# SMeter_RevB.net
KiCad netlist of a schematic drawn in EAGLE
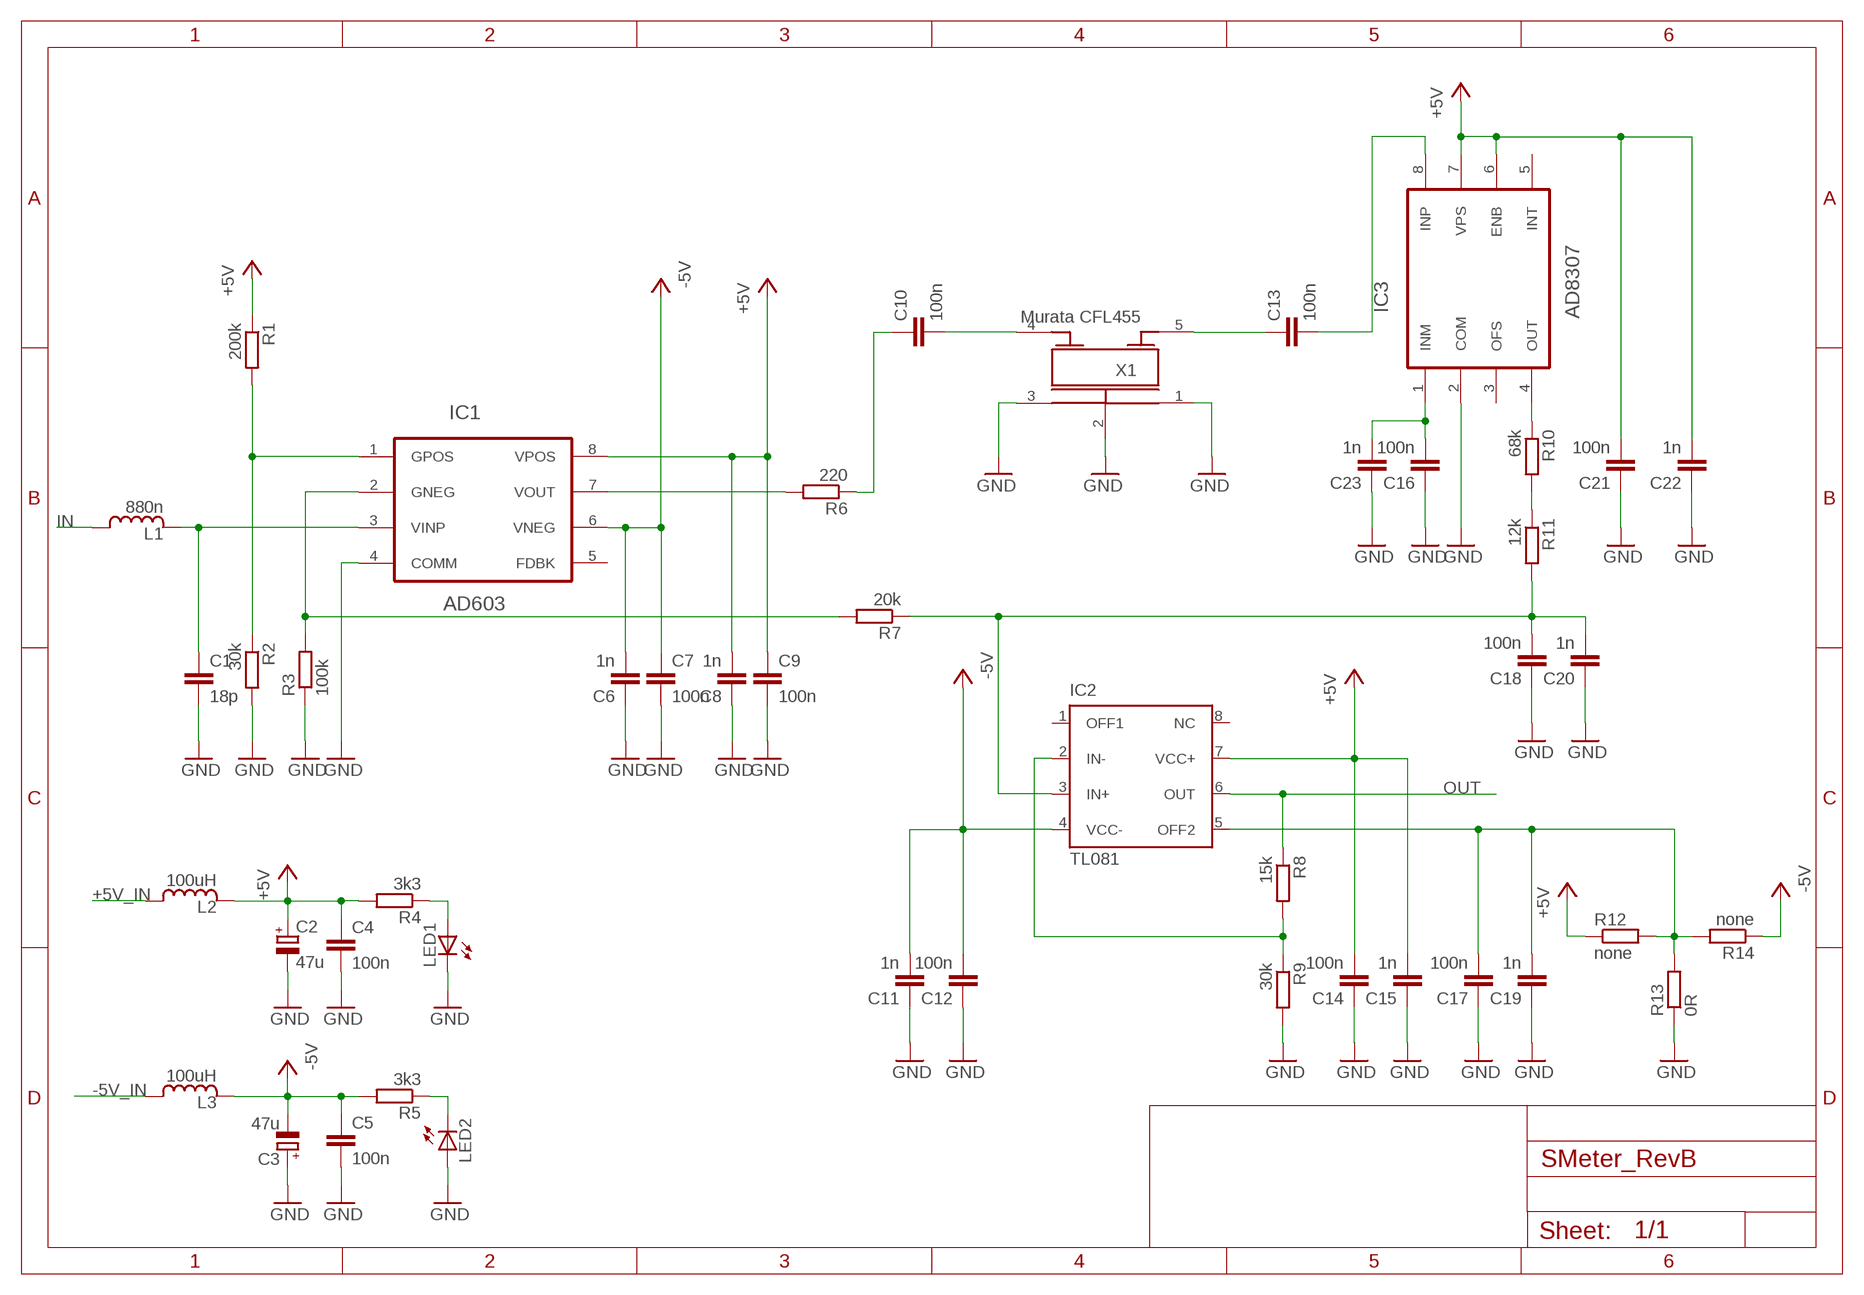
[diagram p0: schematic, sheet 1]

(export (version "E")
  (design (tool "Eeschema 10.0.6"))
  (components
    (comp (ref "C1")
      (value "18p")
      (footprint "eagle-import:C0805")
      (libsource (lib "eagle-import") (part "CC0805"))
    )
    (comp (ref "C2")
      (value "47u")
      (footprint "eagle-import:SMC_B")
      (libsource (lib "eagle-import") (part "C_POLARIZEDSMC_B"))
    )
    (comp (ref "C3")
      (value "47u")
      (footprint "eagle-import:SMC_B")
      (libsource (lib "eagle-import") (part "C_POLARIZEDSMC_B"))
    )
    (comp (ref "C4")
      (value "100n")
      (footprint "eagle-import:C0805")
      (libsource (lib "eagle-import") (part "CC0805"))
    )
    (comp (ref "C5")
      (value "100n")
      (footprint "eagle-import:C0805")
      (libsource (lib "eagle-import") (part "CC0805"))
    )
    (comp (ref "C6")
      (value "1n")
      (footprint "eagle-import:C0805")
      (libsource (lib "eagle-import") (part "CC0805"))
    )
    (comp (ref "C7")
      (value "100n")
      (footprint "eagle-import:C0805")
      (libsource (lib "eagle-import") (part "CC0805"))
    )
    (comp (ref "C8")
      (value "1n")
      (footprint "eagle-import:C0805")
      (libsource (lib "eagle-import") (part "CC0805"))
    )
    (comp (ref "C9")
      (value "100n")
      (footprint "eagle-import:C0805")
      (libsource (lib "eagle-import") (part "CC0805"))
    )
    (comp (ref "C10")
      (value "100n")
      (footprint "eagle-import:C0805")
      (libsource (lib "eagle-import") (part "CC0805"))
    )
    (comp (ref "C11")
      (value "1n")
      (footprint "eagle-import:C0805")
      (libsource (lib "eagle-import") (part "CC0805"))
    )
    (comp (ref "C12")
      (value "100n")
      (footprint "eagle-import:C0805")
      (libsource (lib "eagle-import") (part "CC0805"))
    )
    (comp (ref "C13")
      (value "100n")
      (footprint "eagle-import:C0805")
      (libsource (lib "eagle-import") (part "CC0805"))
    )
    (comp (ref "C14")
      (value "100n")
      (footprint "eagle-import:C0805")
      (libsource (lib "eagle-import") (part "CC0805"))
    )
    (comp (ref "C15")
      (value "1n")
      (footprint "eagle-import:C0805")
      (libsource (lib "eagle-import") (part "CC0805"))
    )
    (comp (ref "C16")
      (value "100n")
      (footprint "eagle-import:C0805")
      (libsource (lib "eagle-import") (part "CC0805"))
    )
    (comp (ref "C17")
      (value "100n")
      (footprint "eagle-import:C0805")
      (libsource (lib "eagle-import") (part "CC0805"))
    )
    (comp (ref "C18")
      (value "100n")
      (footprint "eagle-import:C0805")
      (libsource (lib "eagle-import") (part "CC0805"))
    )
    (comp (ref "C19")
      (value "1n")
      (footprint "eagle-import:C0805")
      (libsource (lib "eagle-import") (part "CC0805"))
    )
    (comp (ref "C20")
      (value "1n")
      (footprint "eagle-import:C0805")
      (libsource (lib "eagle-import") (part "CC0805"))
    )
    (comp (ref "C21")
      (value "100n")
      (footprint "eagle-import:C0805")
      (libsource (lib "eagle-import") (part "CC0805"))
    )
    (comp (ref "C22")
      (value "1n")
      (footprint "eagle-import:C0805")
      (libsource (lib "eagle-import") (part "CC0805"))
    )
    (comp (ref "C23")
      (value "1n")
      (footprint "eagle-import:C0805")
      (libsource (lib "eagle-import") (part "CC0805"))
    )
    (comp (ref "IC1")
      (value "AD603")
      (footprint "eagle-import:SO8")
      (libsource (lib "eagle-import") (part "AD603"))
    )
    (comp (ref "IC2")
      (value "TL081")
      (footprint "eagle-import:SO8")
      (libsource (lib "eagle-import") (part "TL081"))
    )
    (comp (ref "IC3")
      (value "AD8307")
      (footprint "eagle-import:SO8")
      (libsource (lib "eagle-import") (part "AD8307"))
    )
    (comp (ref "L1")
      (value "880n")
      (footprint "eagle-import:L0805")
      (libsource (lib "eagle-import") (part "INDUCTOR0805"))
    )
    (comp (ref "L2")
      (value "100uH")
      (footprint "eagle-import:LPS4018")
      (libsource (lib "eagle-import") (part "INDUCTORLPS4018"))
    )
    (comp (ref "L3")
      (value "100uH")
      (footprint "eagle-import:LPS4018")
      (libsource (lib "eagle-import") (part "INDUCTORLPS4018"))
    )
    (comp (ref "LED1")
      (value "LED0805")
      (footprint "eagle-import:LED0805")
      (libsource (lib "eagle-import") (part "LED0805"))
    )
    (comp (ref "LED2")
      (value "LED0805")
      (footprint "eagle-import:LED0805")
      (libsource (lib "eagle-import") (part "LED0805"))
    )
    (comp (ref "R1")
      (value "200k")
      (footprint "eagle-import:R0805")
      (libsource (lib "eagle-import") (part "RESISTORR0805"))
    )
    (comp (ref "R2")
      (value "30k")
      (footprint "eagle-import:R0805")
      (libsource (lib "eagle-import") (part "RESISTORR0805"))
    )
    (comp (ref "R3")
      (value "100k")
      (footprint "eagle-import:R0805")
      (libsource (lib "eagle-import") (part "RESISTORR0805"))
    )
    (comp (ref "R4")
      (value "3k3")
      (footprint "eagle-import:R0805")
      (libsource (lib "eagle-import") (part "RESISTORR0805"))
    )
    (comp (ref "R5")
      (value "3k3")
      (footprint "eagle-import:R0805")
      (libsource (lib "eagle-import") (part "RESISTORR0805"))
    )
    (comp (ref "R6")
      (value "220")
      (footprint "eagle-import:R0805")
      (libsource (lib "eagle-import") (part "RESISTORR0805"))
    )
    (comp (ref "R7")
      (value "20k")
      (footprint "eagle-import:R0805")
      (libsource (lib "eagle-import") (part "RESISTORR0805"))
    )
    (comp (ref "R8")
      (value "15k")
      (footprint "eagle-import:R0805")
      (libsource (lib "eagle-import") (part "RESISTORR0805"))
    )
    (comp (ref "R9")
      (value "30k")
      (footprint "eagle-import:R0805")
      (libsource (lib "eagle-import") (part "RESISTORR0805"))
    )
    (comp (ref "R10")
      (value "68k")
      (footprint "eagle-import:R0805")
      (libsource (lib "eagle-import") (part "RESISTORR0805"))
    )
    (comp (ref "R11")
      (value "12k")
      (footprint "eagle-import:R0805")
      (libsource (lib "eagle-import") (part "RESISTORR0805"))
    )
    (comp (ref "R12")
      (value "none")
      (footprint "eagle-import:R0805")
      (libsource (lib "eagle-import") (part "RESISTORR0805"))
    )
    (comp (ref "R13")
      (value "0R")
      (footprint "eagle-import:R0805")
      (libsource (lib "eagle-import") (part "RESISTORR0805"))
    )
    (comp (ref "R14")
      (value "none")
      (footprint "eagle-import:R0805")
      (libsource (lib "eagle-import") (part "RESISTORR0805"))
    )
    (comp (ref "X1")
      (value "Murata CFL455")
      (footprint "eagle-import:CFL455")
      (libsource (lib "eagle-import") (part "CFL455"))
    )
  )
  (nets
    (net (code "1") (name "+5V") (class "Default")
      (node (ref "C14") (pin "2") (pinfunction "2_2") (pintype "passive"))
      (node (ref "C15") (pin "2") (pinfunction "2_2") (pintype "passive"))
      (node (ref "C2") (pin "+") (pinfunction "+_+") (pintype "passive"))
      (node (ref "C21") (pin "2") (pinfunction "2_2") (pintype "passive"))
      (node (ref "C22") (pin "2") (pinfunction "2_2") (pintype "passive"))
      (node (ref "C4") (pin "1") (pinfunction "1_1") (pintype "passive"))
      (node (ref "C8") (pin "2") (pinfunction "2_2") (pintype "passive"))
      (node (ref "C9") (pin "1") (pinfunction "1_1") (pintype "passive"))
      (node (ref "IC1") (pin "8") (pinfunction "VPOS_8") (pintype "power_in"))
      (node (ref "IC2") (pin "7") (pinfunction "VCC+_7") (pintype "input"))
      (node (ref "IC3") (pin "6") (pinfunction "ENB_6") (pintype "passive"))
      (node (ref "IC3") (pin "7") (pinfunction "VPS_7") (pintype "passive"))
      (node (ref "L2") (pin "2") (pinfunction "2_2") (pintype "passive"))
      (node (ref "R1") (pin "1") (pinfunction "1_1") (pintype "passive"))
      (node (ref "R12") (pin "1") (pinfunction "1_1") (pintype "passive"))
      (node (ref "R4") (pin "2") (pinfunction "2_2") (pintype "passive"))
    )
    (net (code "2") (name "-5V") (class "Default")
      (node (ref "C11") (pin "2") (pinfunction "2_2") (pintype "passive"))
      (node (ref "C12") (pin "2") (pinfunction "2_2") (pintype "passive"))
      (node (ref "C3") (pin "-") (pinfunction "-_-") (pintype "passive"))
      (node (ref "C5") (pin "1") (pinfunction "1_1") (pintype "passive"))
      (node (ref "C6") (pin "2") (pinfunction "2_2") (pintype "passive"))
      (node (ref "C7") (pin "1") (pinfunction "1_1") (pintype "passive"))
      (node (ref "IC1") (pin "6") (pinfunction "VNEG_6") (pintype "passive"))
      (node (ref "IC2") (pin "4") (pinfunction "VCC-_4") (pintype "power_in"))
      (node (ref "L3") (pin "2") (pinfunction "2_2") (pintype "passive"))
      (node (ref "R14") (pin "1") (pinfunction "1_1") (pintype "passive"))
      (node (ref "R5") (pin "2") (pinfunction "2_2") (pintype "passive"))
    )
    (net (code "3") (name "/+5V_IN") (class "Default")
      (node (ref "L2") (pin "1") (pinfunction "1_1") (pintype "passive"))
    )
    (net (code "4") (name "/-5V_IN") (class "Default")
      (node (ref "L3") (pin "1") (pinfunction "1_1") (pintype "passive"))
    )
    (net (code "5") (name "/IN") (class "Default")
      (node (ref "L1") (pin "1") (pinfunction "1_1") (pintype "passive"))
    )
    (net (code "6") (name "/OUT") (class "Default")
      (node (ref "IC2") (pin "6") (pinfunction "OUT_6") (pintype "passive"))
      (node (ref "R8") (pin "1") (pinfunction "1_1") (pintype "passive"))
    )
    (net (code "7") (name "GND") (class "Default")
      (node (ref "C1") (pin "2") (pinfunction "2_2") (pintype "passive"))
      (node (ref "C11") (pin "1") (pinfunction "1_1") (pintype "passive"))
      (node (ref "C12") (pin "1") (pinfunction "1_1") (pintype "passive"))
      (node (ref "C14") (pin "1") (pinfunction "1_1") (pintype "passive"))
      (node (ref "C15") (pin "1") (pinfunction "1_1") (pintype "passive"))
      (node (ref "C16") (pin "1") (pinfunction "1_1") (pintype "passive"))
      (node (ref "C17") (pin "1") (pinfunction "1_1") (pintype "passive"))
      (node (ref "C18") (pin "1") (pinfunction "1_1") (pintype "passive"))
      (node (ref "C19") (pin "1") (pinfunction "1_1") (pintype "passive"))
      (node (ref "C2") (pin "-") (pinfunction "-_-") (pintype "passive"))
      (node (ref "C20") (pin "1") (pinfunction "1_1") (pintype "passive"))
      (node (ref "C21") (pin "1") (pinfunction "1_1") (pintype "passive"))
      (node (ref "C22") (pin "1") (pinfunction "1_1") (pintype "passive"))
      (node (ref "C23") (pin "1") (pinfunction "1_1") (pintype "passive"))
      (node (ref "C3") (pin "+") (pinfunction "+_+") (pintype "passive"))
      (node (ref "C4") (pin "2") (pinfunction "2_2") (pintype "passive"))
      (node (ref "C5") (pin "2") (pinfunction "2_2") (pintype "passive"))
      (node (ref "C6") (pin "1") (pinfunction "1_1") (pintype "passive"))
      (node (ref "C7") (pin "2") (pinfunction "2_2") (pintype "passive"))
      (node (ref "C8") (pin "1") (pinfunction "1_1") (pintype "passive"))
      (node (ref "C9") (pin "2") (pinfunction "2_2") (pintype "passive"))
      (node (ref "IC1") (pin "4") (pinfunction "COMM_4") (pintype "power_in"))
      (node (ref "IC3") (pin "2") (pinfunction "COM_2") (pintype "input"))
      (node (ref "LED1") (pin "C") (pinfunction "C_C") (pintype "passive"))
      (node (ref "LED2") (pin "A") (pinfunction "A_A") (pintype "passive"))
      (node (ref "R13") (pin "1") (pinfunction "1_1") (pintype "passive"))
      (node (ref "R2") (pin "2") (pinfunction "2_2") (pintype "passive"))
      (node (ref "R3") (pin "1") (pinfunction "1_1") (pintype "passive"))
      (node (ref "R9") (pin "2") (pinfunction "2_2") (pintype "passive"))
      (node (ref "X1") (pin "1") (pinfunction "1_1") (pintype "power_in"))
      (node (ref "X1") (pin "2") (pinfunction "2_2") (pintype "power_in"))
      (node (ref "X1") (pin "3") (pinfunction "3_3") (pintype "power_in"))
    )
    (net (code "8") (name "Net-(C10-Pad1)") (class "Default")
      (node (ref "C10") (pin "1") (pinfunction "1_1") (pintype "passive"))
      (node (ref "R6") (pin "1") (pinfunction "1_1") (pintype "passive"))
    )
    (net (code "9") (name "Net-(C10-Pad2)") (class "Default")
      (node (ref "C10") (pin "2") (pinfunction "2_2") (pintype "passive"))
      (node (ref "X1") (pin "4") (pinfunction "4_4") (pintype "output"))
    )
    (net (code "10") (name "Net-(C13-Pad1)") (class "Default")
      (node (ref "C13") (pin "1") (pinfunction "1_1") (pintype "passive"))
      (node (ref "X1") (pin "5") (pinfunction "5_5") (pintype "input"))
    )
    (net (code "11") (name "Net-(IC1-GNEG)") (class "Default")
      (node (ref "IC1") (pin "2") (pinfunction "GNEG_2") (pintype "input"))
      (node (ref "R3") (pin "2") (pinfunction "2_2") (pintype "passive"))
      (node (ref "R7") (pin "2") (pinfunction "2_2") (pintype "passive"))
    )
    (net (code "12") (name "Net-(IC1-GPOS)") (class "Default")
      (node (ref "IC1") (pin "1") (pinfunction "GPOS_1") (pintype "input"))
      (node (ref "R1") (pin "2") (pinfunction "2_2") (pintype "passive"))
      (node (ref "R2") (pin "1") (pinfunction "1_1") (pintype "passive"))
    )
    (net (code "13") (name "Net-(IC1-VINP)") (class "Default")
      (node (ref "C1") (pin "1") (pinfunction "1_1") (pintype "passive"))
      (node (ref "IC1") (pin "3") (pinfunction "VINP_3") (pintype "bidirectional"))
      (node (ref "L1") (pin "2") (pinfunction "2_2") (pintype "passive"))
    )
    (net (code "14") (name "Net-(IC1-VOUT)") (class "Default")
      (node (ref "IC1") (pin "7") (pinfunction "VOUT_7") (pintype "passive"))
      (node (ref "R6") (pin "2") (pinfunction "2_2") (pintype "passive"))
    )
    (net (code "15") (name "Net-(IC2-IN+)") (class "Default")
      (node (ref "C18") (pin "2") (pinfunction "2_2") (pintype "passive"))
      (node (ref "C20") (pin "2") (pinfunction "2_2") (pintype "passive"))
      (node (ref "IC2") (pin "3") (pinfunction "IN+_3") (pintype "input"))
      (node (ref "R11") (pin "2") (pinfunction "2_2") (pintype "passive"))
      (node (ref "R7") (pin "1") (pinfunction "1_1") (pintype "passive"))
    )
    (net (code "16") (name "Net-(IC2-IN-)") (class "Default")
      (node (ref "IC2") (pin "2") (pinfunction "IN-_2") (pintype "input"))
      (node (ref "R8") (pin "2") (pinfunction "2_2") (pintype "passive"))
      (node (ref "R9") (pin "1") (pinfunction "1_1") (pintype "passive"))
    )
    (net (code "17") (name "Net-(IC2-OFF2)") (class "Default")
      (node (ref "C17") (pin "2") (pinfunction "2_2") (pintype "passive"))
      (node (ref "C19") (pin "2") (pinfunction "2_2") (pintype "passive"))
      (node (ref "IC2") (pin "5") (pinfunction "OFF2_5") (pintype "passive"))
      (node (ref "R12") (pin "2") (pinfunction "2_2") (pintype "passive"))
      (node (ref "R13") (pin "2") (pinfunction "2_2") (pintype "passive"))
      (node (ref "R14") (pin "2") (pinfunction "2_2") (pintype "passive"))
    )
    (net (code "18") (name "Net-(IC3-INM)") (class "Default")
      (node (ref "C16") (pin "2") (pinfunction "2_2") (pintype "passive"))
      (node (ref "C23") (pin "2") (pinfunction "2_2") (pintype "passive"))
      (node (ref "IC3") (pin "1") (pinfunction "INM_1") (pintype "input"))
    )
    (net (code "19") (name "Net-(IC3-INP)") (class "Default")
      (node (ref "C13") (pin "2") (pinfunction "2_2") (pintype "passive"))
      (node (ref "IC3") (pin "8") (pinfunction "INP_8") (pintype "power_in"))
    )
    (net (code "20") (name "Net-(IC3-OUT)") (class "Default")
      (node (ref "IC3") (pin "4") (pinfunction "OUT_4") (pintype "power_in"))
      (node (ref "R10") (pin "1") (pinfunction "1_1") (pintype "passive"))
    )
    (net (code "21") (name "Net-(LED1-PadA)") (class "Default")
      (node (ref "LED1") (pin "A") (pinfunction "A_A") (pintype "passive"))
      (node (ref "R4") (pin "1") (pinfunction "1_1") (pintype "passive"))
    )
    (net (code "22") (name "Net-(LED2-PadC)") (class "Default")
      (node (ref "LED2") (pin "C") (pinfunction "C_C") (pintype "passive"))
      (node (ref "R5") (pin "1") (pinfunction "1_1") (pintype "passive"))
    )
    (net (code "23") (name "Net-(R10-Pad2)") (class "Default")
      (node (ref "R10") (pin "2") (pinfunction "2_2") (pintype "passive"))
      (node (ref "R11") (pin "1") (pinfunction "1_1") (pintype "passive"))
    )
    (net (code "24") (name "unconnected-(IC1-FDBK-Pad5)") (class "Default")
      (node (ref "IC1") (pin "5") (pinfunction "FDBK_5") (pintype "passive"))
    )
    (net (code "25") (name "unconnected-(IC2-NC-Pad8)") (class "Default")
      (node (ref "IC2") (pin "8") (pinfunction "NC_8") (pintype "input"))
    )
    (net (code "26") (name "unconnected-(IC2-OFF1-Pad1)") (class "Default")
      (node (ref "IC2") (pin "1") (pinfunction "OFF1_1") (pintype "input"))
    )
    (net (code "27") (name "unconnected-(IC3-INT-Pad5)") (class "Default")
      (node (ref "IC3") (pin "5") (pinfunction "INT_5") (pintype "passive"))
    )
    (net (code "28") (name "unconnected-(IC3-OFS-Pad3)") (class "Default")
      (node (ref "IC3") (pin "3") (pinfunction "OFS_3") (pintype "bidirectional"))
    )
  )
)
